# 6_uart_esc_i2c.net
KiCad netlist of a schematic drawn in Altium Designer
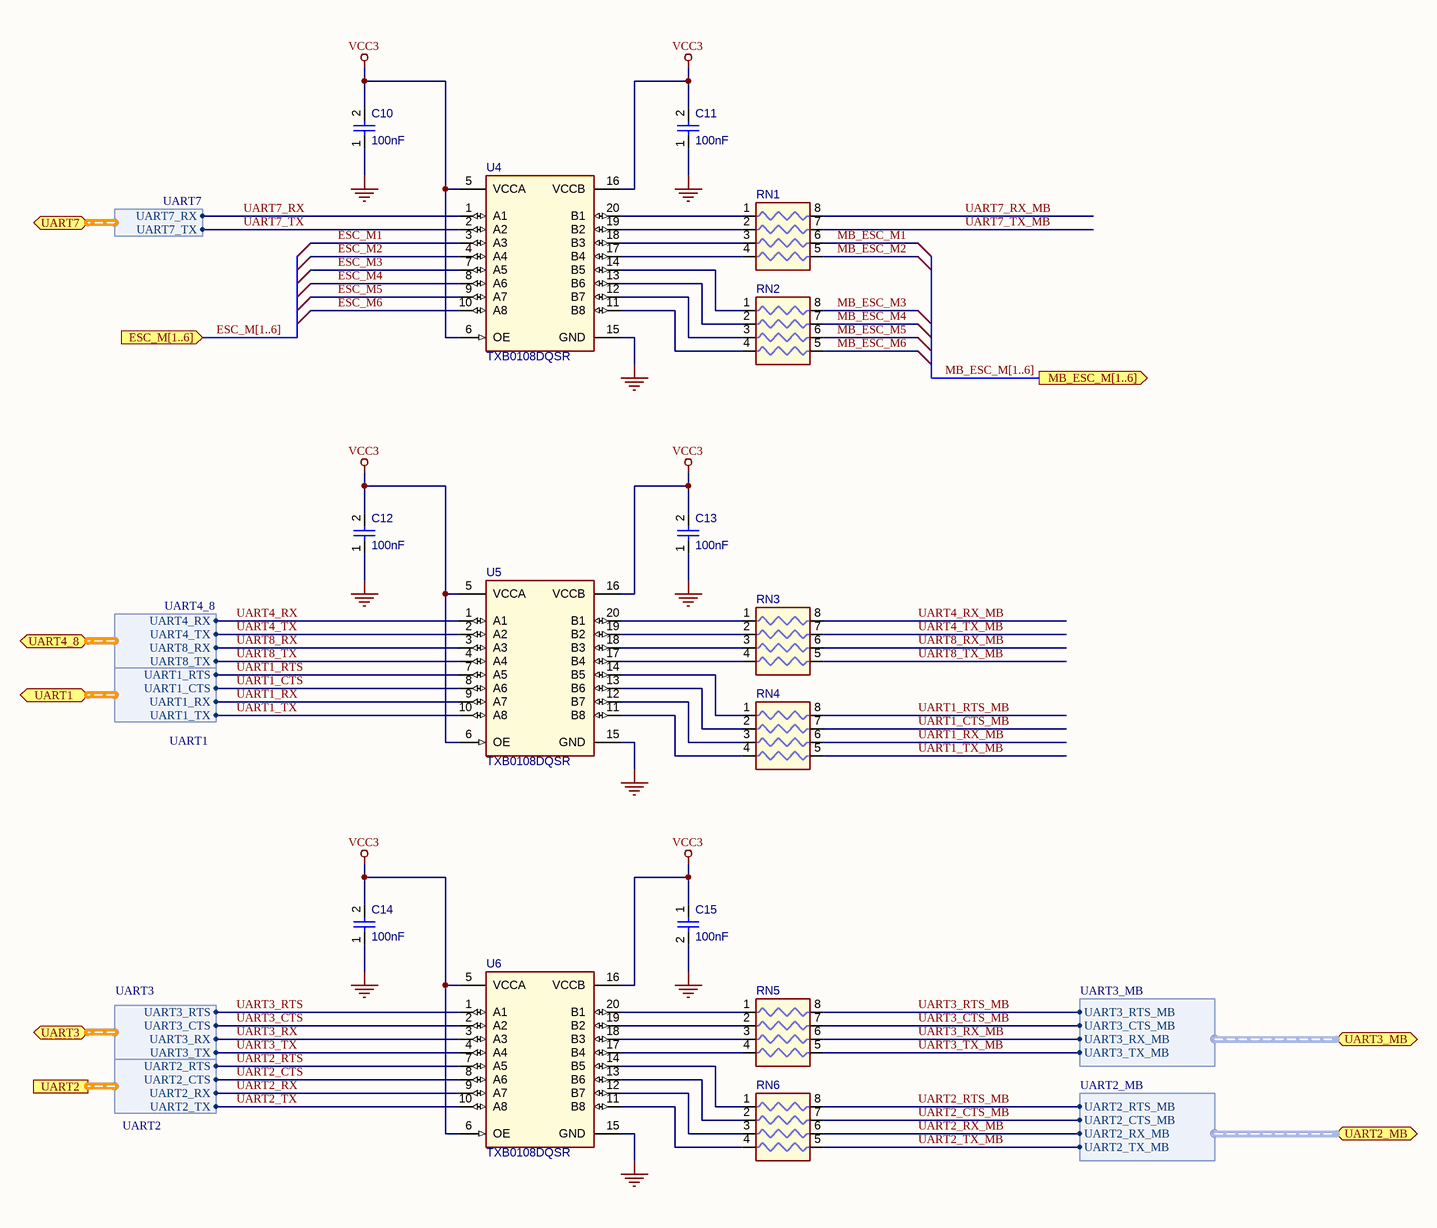
[diagram p0: 6_uart_esc_i2c.SchDoc]

(export (version "E")
  (design (tool "Eeschema 10.0.6"))
  (components
    (comp (ref "C10")
      (value "100nF")
      (footprint "CAPC0402(1005)60_L")
      (description "Chip Capacitor, 100nF +/-20%, 10V, 0402, Thickness 0.6 mm")
      (fields (field (name "TOLERANCE") "20%") (field (name "Comment") "Capacitor 100nF +/-20% 10V 0402"))
      (libsource (lib "<Company> Server") (part "CAP-NP-2"))
    )
    (comp (ref "C11")
      (value "100nF")
      (footprint "CAPC0402(1005)60_L")
      (description "Chip Capacitor, 100nF +/-20%, 10V, 0402, Thickness 0.6 mm")
      (fields (field (name "TOLERANCE") "20%") (field (name "Comment") "Capacitor 100nF +/-20% 10V 0402"))
      (libsource (lib "<Company> Server") (part "CAP-NP-2"))
    )
    (comp (ref "C12")
      (value "100nF")
      (footprint "CAPC0402(1005)60_L")
      (description "Chip Capacitor, 100nF +/-20%, 10V, 0402, Thickness 0.6 mm")
      (fields (field (name "TOLERANCE") "20%") (field (name "Comment") "Capacitor 100nF +/-20% 10V 0402"))
      (libsource (lib "<Company> Server") (part "CAP-NP-2"))
    )
    (comp (ref "C13")
      (value "100nF")
      (footprint "CAPC0402(1005)60_L")
      (description "Chip Capacitor, 100nF +/-20%, 10V, 0402, Thickness 0.6 mm")
      (fields (field (name "TOLERANCE") "20%") (field (name "Comment") "Capacitor 100nF +/-20% 10V 0402"))
      (libsource (lib "<Company> Server") (part "CAP-NP-2"))
    )
    (comp (ref "C14")
      (value "100nF")
      (footprint "CAPC0402(1005)60_L")
      (description "Chip Capacitor, 100nF +/-20%, 10V, 0402, Thickness 0.6 mm")
      (fields (field (name "TOLERANCE") "20%") (field (name "Comment") "Capacitor 100nF +/-20% 10V 0402"))
      (libsource (lib "<Company> Server") (part "CAP-NP-2"))
    )
    (comp (ref "C15")
      (value "100nF")
      (footprint "CAPC0402(1005)60_L")
      (description "Chip Capacitor, 100nF +/-20%, 10V, 0402, Thickness 0.6 mm")
      (fields (field (name "TOLERANCE") "20%") (field (name "Comment") "Capacitor 100nF +/-20% 10V 0402"))
      (libsource (lib "<Company> Server") (part "CAP-NP-2"))
    )
    (comp (ref "RN1")
      (value "Resistor 200R +/-5% 0402 62.5 mW")
      (footprint "Panasonic_EXB28")
      (fields (field (name "TOLERANCE") "5%") (field (name "POWER") "62.5mW"))
      (libsource (lib "<Company> Server") (part "RES-P-4"))
    )
    (comp (ref "RN2")
      (value "Resistor 200R +/-5% 0402 62.5 mW")
      (footprint "Panasonic_EXB28")
      (fields (field (name "TOLERANCE") "5%") (field (name "POWER") "62.5mW"))
      (libsource (lib "<Company> Server") (part "RES-P-4"))
    )
    (comp (ref "RN3")
      (value "Resistor 200R +/-5% 0402 62.5 mW")
      (footprint "Panasonic_EXB28")
      (fields (field (name "TOLERANCE") "5%") (field (name "POWER") "62.5mW"))
      (libsource (lib "<Company> Server") (part "RES-P-4"))
    )
    (comp (ref "RN4")
      (value "Resistor 200R +/-5% 0402 62.5 mW")
      (footprint "Panasonic_EXB28")
      (fields (field (name "TOLERANCE") "5%") (field (name "POWER") "62.5mW"))
      (libsource (lib "<Company> Server") (part "RES-P-4"))
    )
    (comp (ref "RN5")
      (value "Resistor 200R +/-5% 0402 62.5 mW")
      (footprint "Panasonic_EXB28")
      (fields (field (name "TOLERANCE") "5%") (field (name "POWER") "62.5mW"))
      (libsource (lib "<Company> Server") (part "RES-P-4"))
    )
    (comp (ref "RN6")
      (value "Resistor 200R +/-5% 0402 62.5 mW")
      (footprint "Panasonic_EXB28")
      (fields (field (name "TOLERANCE") "5%") (field (name "POWER") "62.5mW"))
      (libsource (lib "<Company> Server") (part "RES-P-4"))
    )
    (comp (ref "U4")
      (value "TXB0108DQSR")
      (footprint "DQS0020A_V")
      (libsource (lib "<Company> Server") (part "CMP-00162-7"))
    )
    (comp (ref "U5")
      (value "TXB0108DQSR")
      (footprint "DQS0020A_V")
      (libsource (lib "<Company> Server") (part "CMP-00162-7"))
    )
    (comp (ref "U6")
      (value "TXB0108DQSR")
      (footprint "DQS0020A_V")
      (libsource (lib "<Company> Server") (part "CMP-00162-7"))
    )
  )
  (nets
    (net (code "8") (name "/ESC_M1") (class "Default")
      (node (ref "U4") (pin "3") (pinfunction "A3_3") (pintype "bidirectional"))
    )
    (net (code "9") (name "/ESC_M2") (class "Default")
      (node (ref "U4") (pin "4") (pinfunction "A4_4") (pintype "bidirectional"))
    )
    (net (code "10") (name "/ESC_M3") (class "Default")
      (node (ref "U4") (pin "7") (pinfunction "A5_7") (pintype "bidirectional"))
    )
    (net (code "11") (name "/ESC_M4") (class "Default")
      (node (ref "U4") (pin "8") (pinfunction "A6_8") (pintype "bidirectional"))
    )
    (net (code "12") (name "/ESC_M5") (class "Default")
      (node (ref "U4") (pin "9") (pinfunction "A7_9") (pintype "bidirectional"))
    )
    (net (code "13") (name "/ESC_M6") (class "Default")
      (node (ref "U4") (pin "10") (pinfunction "A8_10") (pintype "bidirectional"))
    )
    (net (code "15") (name "/MB_ESC_M1") (class "Default")
      (node (ref "RN1") (pin "6") (pinfunction "2_6") (pintype "passive"))
    )
    (net (code "16") (name "/MB_ESC_M2") (class "Default")
      (node (ref "RN1") (pin "5") (pinfunction "2_5") (pintype "passive"))
    )
    (net (code "17") (name "/MB_ESC_M3") (class "Default")
      (node (ref "RN2") (pin "8") (pinfunction "2_8") (pintype "passive"))
    )
    (net (code "18") (name "/MB_ESC_M4") (class "Default")
      (node (ref "RN2") (pin "7") (pinfunction "2_7") (pintype "passive"))
    )
    (net (code "19") (name "/MB_ESC_M5") (class "Default")
      (node (ref "RN2") (pin "6") (pinfunction "2_6") (pintype "passive"))
    )
    (net (code "20") (name "/MB_ESC_M6") (class "Default")
      (node (ref "RN2") (pin "5") (pinfunction "2_5") (pintype "passive"))
    )
    (net (code "22") (name "/UART1_CTS") (class "Default")
      (node (ref "U5") (pin "8") (pinfunction "A6_8") (pintype "bidirectional"))
    )
    (net (code "23") (name "/UART1_CTS_MB") (class "Default")
      (node (ref "RN4") (pin "7") (pinfunction "2_7") (pintype "passive"))
    )
    (net (code "24") (name "/UART1_RTS") (class "Default")
      (node (ref "U5") (pin "7") (pinfunction "A5_7") (pintype "bidirectional"))
    )
    (net (code "25") (name "/UART1_RTS_MB") (class "Default")
      (node (ref "RN4") (pin "8") (pinfunction "2_8") (pintype "passive"))
    )
    (net (code "26") (name "/UART1_RX") (class "Default")
      (node (ref "U5") (pin "9") (pinfunction "A7_9") (pintype "bidirectional"))
    )
    (net (code "27") (name "/UART1_RX_MB") (class "Default")
      (node (ref "RN4") (pin "6") (pinfunction "2_6") (pintype "passive"))
    )
    (net (code "28") (name "/UART1_TX") (class "Default")
      (node (ref "U5") (pin "10") (pinfunction "A8_10") (pintype "bidirectional"))
    )
    (net (code "29") (name "/UART1_TX_MB") (class "Default")
      (node (ref "RN4") (pin "5") (pinfunction "2_5") (pintype "passive"))
    )
    (net (code "30") (name "/UART2_CTS") (class "Default")
      (node (ref "U6") (pin "8") (pinfunction "A6_8") (pintype "bidirectional"))
    )
    (net (code "31") (name "/UART2_CTS_MB") (class "Default")
      (node (ref "RN6") (pin "7") (pinfunction "2_7") (pintype "passive"))
    )
    (net (code "32") (name "/UART2_RTS") (class "Default")
      (node (ref "U6") (pin "7") (pinfunction "A5_7") (pintype "bidirectional"))
    )
    (net (code "33") (name "/UART2_RTS_MB") (class "Default")
      (node (ref "RN6") (pin "8") (pinfunction "2_8") (pintype "passive"))
    )
    (net (code "34") (name "/UART2_RX") (class "Default")
      (node (ref "U6") (pin "9") (pinfunction "A7_9") (pintype "bidirectional"))
    )
    (net (code "35") (name "/UART2_RX_MB") (class "Default")
      (node (ref "RN6") (pin "6") (pinfunction "2_6") (pintype "passive"))
    )
    (net (code "36") (name "/UART2_TX") (class "Default")
      (node (ref "U6") (pin "10") (pinfunction "A8_10") (pintype "bidirectional"))
    )
    (net (code "37") (name "/UART2_TX_MB") (class "Default")
      (node (ref "RN6") (pin "5") (pinfunction "2_5") (pintype "passive"))
    )
    (net (code "38") (name "/UART3_CTS") (class "Default")
      (node (ref "U6") (pin "2") (pinfunction "A2_2") (pintype "bidirectional"))
    )
    (net (code "39") (name "/UART3_CTS_MB") (class "Default")
      (node (ref "RN5") (pin "7") (pinfunction "2_7") (pintype "passive"))
    )
    (net (code "40") (name "/UART3_RTS") (class "Default")
      (node (ref "U6") (pin "1") (pinfunction "A1_1") (pintype "bidirectional"))
    )
    (net (code "41") (name "/UART3_RTS_MB") (class "Default")
      (node (ref "RN5") (pin "8") (pinfunction "2_8") (pintype "passive"))
    )
    (net (code "42") (name "/UART3_RX") (class "Default")
      (node (ref "U6") (pin "3") (pinfunction "A3_3") (pintype "bidirectional"))
    )
    (net (code "43") (name "/UART3_RX_MB") (class "Default")
      (node (ref "RN5") (pin "6") (pinfunction "2_6") (pintype "passive"))
    )
    (net (code "44") (name "/UART3_TX") (class "Default")
      (node (ref "U6") (pin "4") (pinfunction "A4_4") (pintype "bidirectional"))
    )
    (net (code "45") (name "/UART3_TX_MB") (class "Default")
      (node (ref "RN5") (pin "5") (pinfunction "2_5") (pintype "passive"))
    )
    (net (code "46") (name "/UART4_RX") (class "Default")
      (node (ref "U5") (pin "1") (pinfunction "A1_1") (pintype "bidirectional"))
    )
    (net (code "47") (name "/UART4_RX_MB") (class "Default")
      (node (ref "RN3") (pin "8") (pinfunction "2_8") (pintype "passive"))
    )
    (net (code "48") (name "/UART4_TX") (class "Default")
      (node (ref "U5") (pin "2") (pinfunction "A2_2") (pintype "bidirectional"))
    )
    (net (code "49") (name "/UART4_TX_MB") (class "Default")
      (node (ref "RN3") (pin "7") (pinfunction "2_7") (pintype "passive"))
    )
    (net (code "50") (name "/UART7_RX") (class "Default")
      (node (ref "U4") (pin "1") (pinfunction "A1_1") (pintype "bidirectional"))
    )
    (net (code "51") (name "/UART7_RX_MB") (class "Default")
      (node (ref "RN1") (pin "8") (pinfunction "2_8") (pintype "passive"))
    )
    (net (code "52") (name "/UART7_TX") (class "Default")
      (node (ref "U4") (pin "2") (pinfunction "A2_2") (pintype "bidirectional"))
    )
    (net (code "53") (name "/UART7_TX_MB") (class "Default")
      (node (ref "RN1") (pin "7") (pinfunction "2_7") (pintype "passive"))
    )
    (net (code "54") (name "/UART8_RX") (class "Default")
      (node (ref "U5") (pin "3") (pinfunction "A3_3") (pintype "bidirectional"))
    )
    (net (code "55") (name "/UART8_RX_MB") (class "Default")
      (node (ref "RN3") (pin "6") (pinfunction "2_6") (pintype "passive"))
    )
    (net (code "56") (name "/UART8_TX") (class "Default")
      (node (ref "U5") (pin "4") (pinfunction "A4_4") (pintype "bidirectional"))
    )
    (net (code "57") (name "/UART8_TX_MB") (class "Default")
      (node (ref "RN3") (pin "5") (pinfunction "2_5") (pintype "passive"))
    )
    (net (code "65") (name "GND") (class "Default")
      (node (ref "C10") (pin "1") (pinfunction "1_1") (pintype "passive"))
      (node (ref "C11") (pin "1") (pinfunction "1_1") (pintype "passive"))
      (node (ref "C12") (pin "1") (pinfunction "1_1") (pintype "passive"))
      (node (ref "C13") (pin "1") (pinfunction "1_1") (pintype "passive"))
      (node (ref "C14") (pin "1") (pinfunction "1_1") (pintype "passive"))
      (node (ref "C15") (pin "2") (pinfunction "2_2") (pintype "passive"))
      (node (ref "U4") (pin "15") (pinfunction "GND_15") (pintype "power_in"))
      (node (ref "U5") (pin "15") (pinfunction "GND_15") (pintype "power_in"))
      (node (ref "U6") (pin "15") (pinfunction "GND_15") (pintype "power_in"))
    )
    (net (code "66") (name "Net-(U4-B1)") (class "Default")
      (node (ref "RN1") (pin "1") (pinfunction "1_1") (pintype "passive"))
      (node (ref "U4") (pin "20") (pinfunction "B1_20") (pintype "bidirectional"))
    )
    (net (code "67") (name "Net-(U4-B2)") (class "Default")
      (node (ref "RN1") (pin "2") (pinfunction "1_2") (pintype "passive"))
      (node (ref "U4") (pin "19") (pinfunction "B2_19") (pintype "bidirectional"))
    )
    (net (code "68") (name "Net-(U4-B3)") (class "Default")
      (node (ref "RN1") (pin "3") (pinfunction "1_3") (pintype "passive"))
      (node (ref "U4") (pin "18") (pinfunction "B3_18") (pintype "bidirectional"))
    )
    (net (code "69") (name "Net-(U4-B4)") (class "Default")
      (node (ref "RN1") (pin "4") (pinfunction "1_4") (pintype "passive"))
      (node (ref "U4") (pin "17") (pinfunction "B4_17") (pintype "bidirectional"))
    )
    (net (code "70") (name "Net-(U4-B5)") (class "Default")
      (node (ref "RN2") (pin "1") (pinfunction "1_1") (pintype "passive"))
      (node (ref "U4") (pin "14") (pinfunction "B5_14") (pintype "bidirectional"))
    )
    (net (code "71") (name "Net-(U4-B6)") (class "Default")
      (node (ref "RN2") (pin "2") (pinfunction "1_2") (pintype "passive"))
      (node (ref "U4") (pin "13") (pinfunction "B6_13") (pintype "bidirectional"))
    )
    (net (code "72") (name "Net-(U4-B7)") (class "Default")
      (node (ref "RN2") (pin "3") (pinfunction "1_3") (pintype "passive"))
      (node (ref "U4") (pin "12") (pinfunction "B7_12") (pintype "bidirectional"))
    )
    (net (code "73") (name "Net-(U4-B8)") (class "Default")
      (node (ref "RN2") (pin "4") (pinfunction "1_4") (pintype "passive"))
      (node (ref "U4") (pin "11") (pinfunction "B8_11") (pintype "bidirectional"))
    )
    (net (code "74") (name "Net-(U5-B1)") (class "Default")
      (node (ref "RN3") (pin "1") (pinfunction "1_1") (pintype "passive"))
      (node (ref "U5") (pin "20") (pinfunction "B1_20") (pintype "bidirectional"))
    )
    (net (code "75") (name "Net-(U5-B2)") (class "Default")
      (node (ref "RN3") (pin "2") (pinfunction "1_2") (pintype "passive"))
      (node (ref "U5") (pin "19") (pinfunction "B2_19") (pintype "bidirectional"))
    )
    (net (code "76") (name "Net-(U5-B3)") (class "Default")
      (node (ref "RN3") (pin "3") (pinfunction "1_3") (pintype "passive"))
      (node (ref "U5") (pin "18") (pinfunction "B3_18") (pintype "bidirectional"))
    )
    (net (code "77") (name "Net-(U5-B4)") (class "Default")
      (node (ref "RN3") (pin "4") (pinfunction "1_4") (pintype "passive"))
      (node (ref "U5") (pin "17") (pinfunction "B4_17") (pintype "bidirectional"))
    )
    (net (code "78") (name "Net-(U5-B5)") (class "Default")
      (node (ref "RN4") (pin "1") (pinfunction "1_1") (pintype "passive"))
      (node (ref "U5") (pin "14") (pinfunction "B5_14") (pintype "bidirectional"))
    )
    (net (code "79") (name "Net-(U5-B6)") (class "Default")
      (node (ref "RN4") (pin "2") (pinfunction "1_2") (pintype "passive"))
      (node (ref "U5") (pin "13") (pinfunction "B6_13") (pintype "bidirectional"))
    )
    (net (code "80") (name "Net-(U5-B7)") (class "Default")
      (node (ref "RN4") (pin "3") (pinfunction "1_3") (pintype "passive"))
      (node (ref "U5") (pin "12") (pinfunction "B7_12") (pintype "bidirectional"))
    )
    (net (code "81") (name "Net-(U5-B8)") (class "Default")
      (node (ref "RN4") (pin "4") (pinfunction "1_4") (pintype "passive"))
      (node (ref "U5") (pin "11") (pinfunction "B8_11") (pintype "bidirectional"))
    )
    (net (code "82") (name "Net-(U6-B1)") (class "Default")
      (node (ref "RN5") (pin "1") (pinfunction "1_1") (pintype "passive"))
      (node (ref "U6") (pin "20") (pinfunction "B1_20") (pintype "bidirectional"))
    )
    (net (code "83") (name "Net-(U6-B2)") (class "Default")
      (node (ref "RN5") (pin "2") (pinfunction "1_2") (pintype "passive"))
      (node (ref "U6") (pin "19") (pinfunction "B2_19") (pintype "bidirectional"))
    )
    (net (code "84") (name "Net-(U6-B3)") (class "Default")
      (node (ref "RN5") (pin "3") (pinfunction "1_3") (pintype "passive"))
      (node (ref "U6") (pin "18") (pinfunction "B3_18") (pintype "bidirectional"))
    )
    (net (code "85") (name "Net-(U6-B4)") (class "Default")
      (node (ref "RN5") (pin "4") (pinfunction "1_4") (pintype "passive"))
      (node (ref "U6") (pin "17") (pinfunction "B4_17") (pintype "bidirectional"))
    )
    (net (code "86") (name "Net-(U6-B5)") (class "Default")
      (node (ref "RN6") (pin "1") (pinfunction "1_1") (pintype "passive"))
      (node (ref "U6") (pin "14") (pinfunction "B5_14") (pintype "bidirectional"))
    )
    (net (code "87") (name "Net-(U6-B6)") (class "Default")
      (node (ref "RN6") (pin "2") (pinfunction "1_2") (pintype "passive"))
      (node (ref "U6") (pin "13") (pinfunction "B6_13") (pintype "bidirectional"))
    )
    (net (code "88") (name "Net-(U6-B7)") (class "Default")
      (node (ref "RN6") (pin "3") (pinfunction "1_3") (pintype "passive"))
      (node (ref "U6") (pin "12") (pinfunction "B7_12") (pintype "bidirectional"))
    )
    (net (code "89") (name "Net-(U6-B8)") (class "Default")
      (node (ref "RN6") (pin "4") (pinfunction "1_4") (pintype "passive"))
      (node (ref "U6") (pin "11") (pinfunction "B8_11") (pintype "bidirectional"))
    )
    (net (code "90") (name "VCC3") (class "Default")
      (node (ref "C10") (pin "2") (pinfunction "2_2") (pintype "passive"))
      (node (ref "C11") (pin "2") (pinfunction "2_2") (pintype "passive"))
      (node (ref "C12") (pin "2") (pinfunction "2_2") (pintype "passive"))
      (node (ref "C13") (pin "2") (pinfunction "2_2") (pintype "passive"))
      (node (ref "C14") (pin "2") (pinfunction "2_2") (pintype "passive"))
      (node (ref "C15") (pin "1") (pinfunction "1_1") (pintype "passive"))
      (node (ref "U4") (pin "16") (pinfunction "VCCB_16") (pintype "power_in"))
      (node (ref "U4") (pin "5") (pinfunction "VCCA_5") (pintype "power_in"))
      (node (ref "U4") (pin "6") (pinfunction "OE_6") (pintype "input"))
      (node (ref "U5") (pin "16") (pinfunction "VCCB_16") (pintype "power_in"))
      (node (ref "U5") (pin "5") (pinfunction "VCCA_5") (pintype "power_in"))
      (node (ref "U5") (pin "6") (pinfunction "OE_6") (pintype "input"))
      (node (ref "U6") (pin "16") (pinfunction "VCCB_16") (pintype "power_in"))
      (node (ref "U6") (pin "5") (pinfunction "VCCA_5") (pintype "power_in"))
      (node (ref "U6") (pin "6") (pinfunction "OE_6") (pintype "input"))
    )
  )
)
